# tinyLight_v1_1.net
KiCad netlist of a schematic drawn in EAGLE
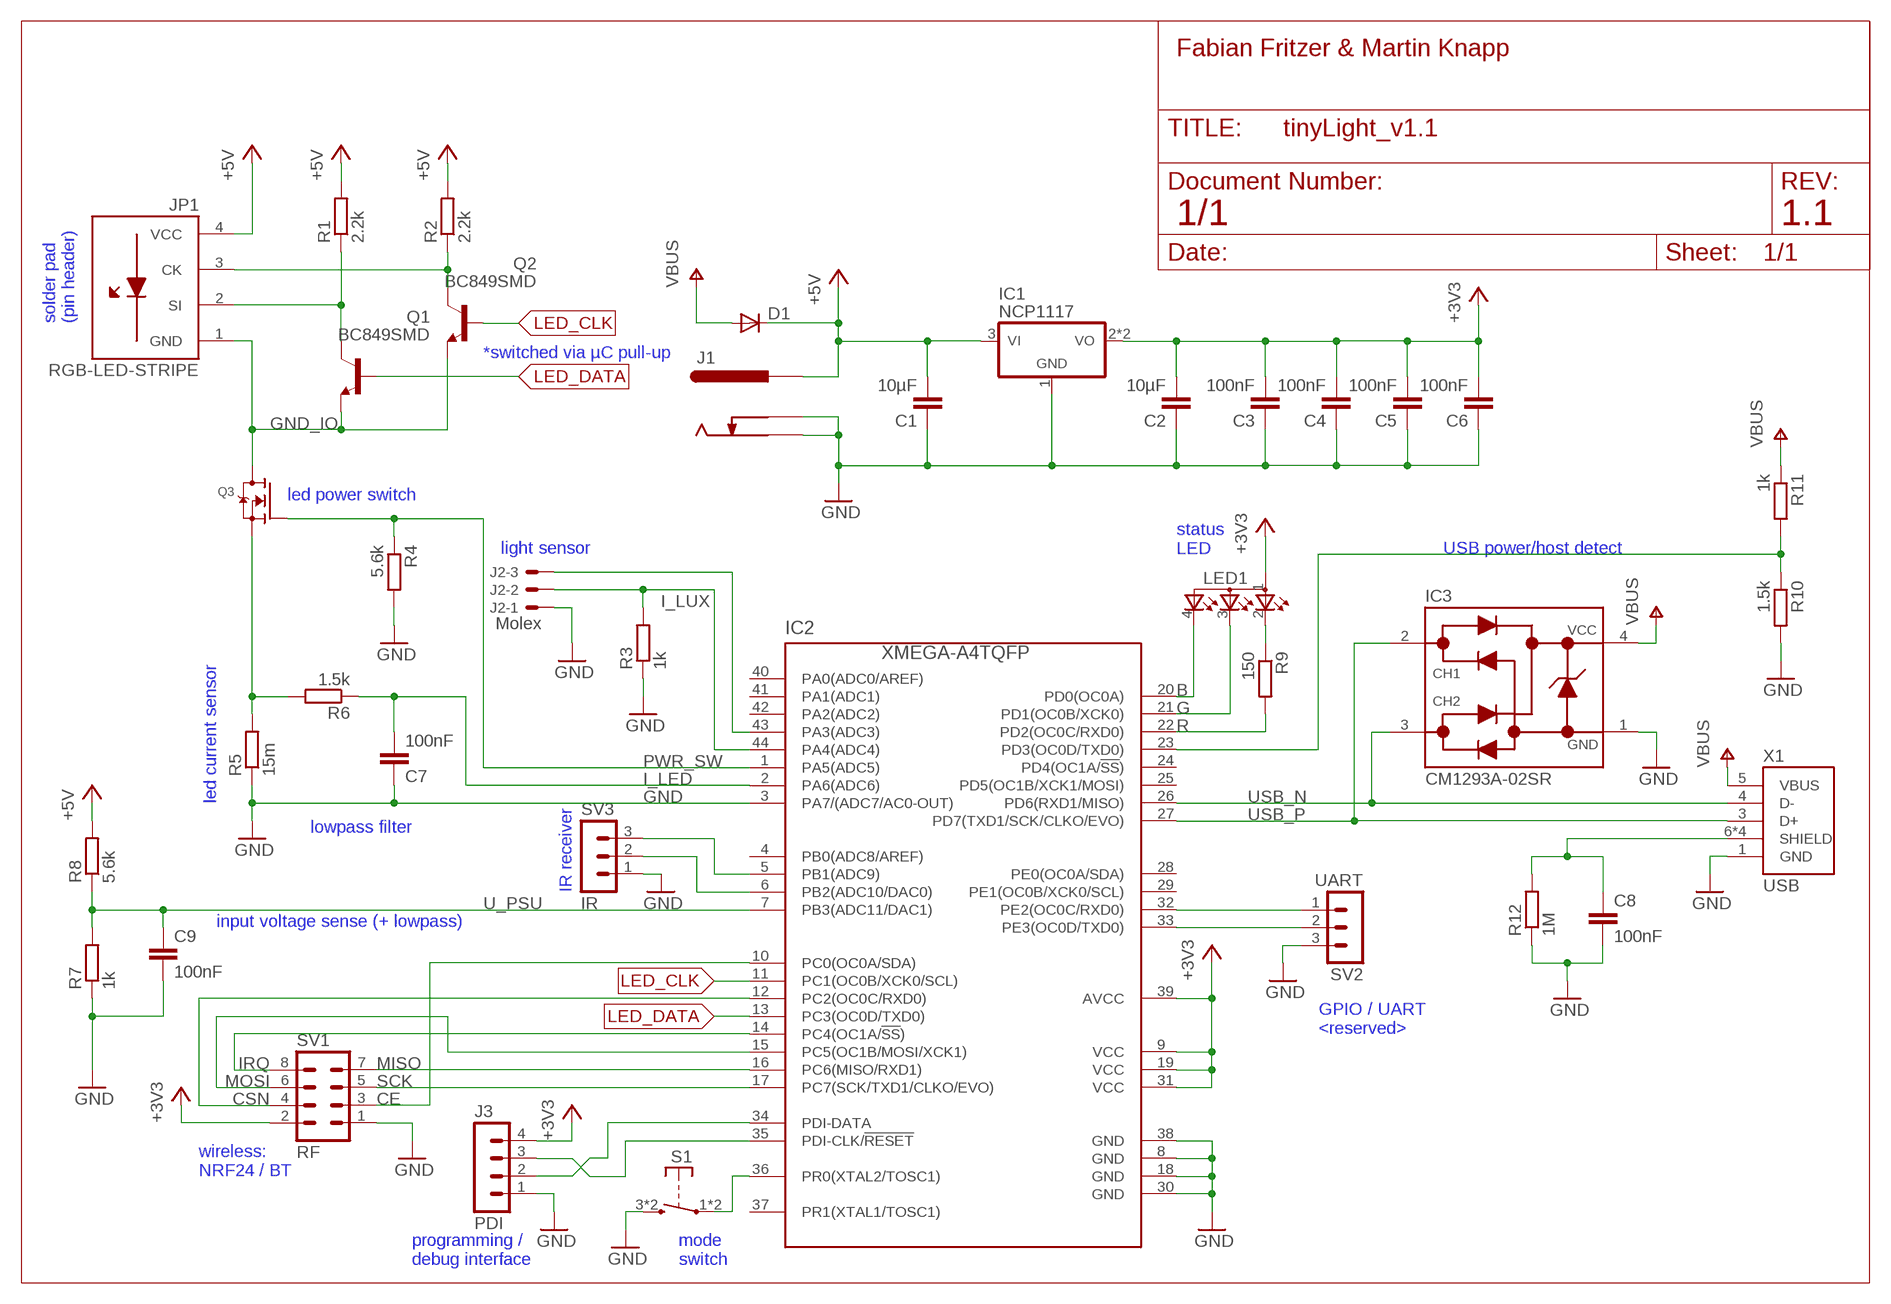
[diagram p0: schematic, sheet 1]

(export (version "E")
  (design (tool "Eeschema 10.0.6"))
  (components
    (comp (ref "C1")
      (value "10µF")
      (footprint "eagle-import:C2012")
      (libsource (lib "eagle-import") (part "C-EUC2012"))
    )
    (comp (ref "C2")
      (value "10µF")
      (footprint "eagle-import:C2012")
      (libsource (lib "eagle-import") (part "C-EUC2012"))
    )
    (comp (ref "C3")
      (value "100nF")
      (footprint "eagle-import:C2012")
      (libsource (lib "eagle-import") (part "C-EUC2012"))
    )
    (comp (ref "C4")
      (value "100nF")
      (footprint "eagle-import:C2012")
      (libsource (lib "eagle-import") (part "C-EUC2012"))
    )
    (comp (ref "C5")
      (value "100nF")
      (footprint "eagle-import:C2012")
      (libsource (lib "eagle-import") (part "C-EUC2012"))
    )
    (comp (ref "C6")
      (value "100nF")
      (footprint "eagle-import:C2012")
      (libsource (lib "eagle-import") (part "C-EUC2012"))
    )
    (comp (ref "C7")
      (value "100nF")
      (footprint "eagle-import:C2012")
      (libsource (lib "eagle-import") (part "C-EUC2012"))
    )
    (comp (ref "C8")
      (value "100nF")
      (footprint "eagle-import:C2012")
      (libsource (lib "eagle-import") (part "C-EUC2012"))
    )
    (comp (ref "C9")
      (value "100nF")
      (footprint "eagle-import:C2012")
      (libsource (lib "eagle-import") (part "C-EUC2012"))
    )
    (comp (ref "D1")
      (value "DIODE-DO-214AC")
      (footprint "eagle-import:DO-214AC")
      (libsource (lib "eagle-import") (part "DIODE-DO-214AC"))
    )
    (comp (ref "IC1")
      (value "NCP1117")
      (footprint "eagle-import:SOT223")
      (libsource (lib "eagle-import") (part "NCP1117"))
    )
    (comp (ref "IC2")
      (value "XMEGA-A4TQFP")
      (footprint "eagle-import:TQFP44")
      (libsource (lib "eagle-import") (part "XMEGA-A4TQFP"))
    )
    (comp (ref "IC3")
      (value "CM1293A-02SR")
      (footprint "eagle-import:SOT143")
      (libsource (lib "eagle-import") (part "CM1293A-02SR"))
    )
    (comp (ref "J1")
      (value "RASM722PX")
      (footprint "eagle-import:RASM722PX")
      (libsource (lib "eagle-import") (part "RASM722PX"))
    )
    (comp (ref "J2")
      (value "Molex")
      (footprint "eagle-import:6410-03")
      (libsource (lib "eagle-import") (part "22-?-0327-2031"))
    )
    (comp (ref "J3")
      (value "PDI")
      (footprint "eagle-import:MA04-1")
      (libsource (lib "eagle-import") (part "MA04-1"))
    )
    (comp (ref "JP1")
      (value "RGB-LED-STRIPE")
      (footprint "eagle-import:LED-STRIPE")
      (libsource (lib "eagle-import") (part "RGB-LED-STRIPE"))
    )
    (comp (ref "LED1")
      (value "RGB-LEDMINI")
      (footprint "eagle-import:P-LCC-4_M")
      (libsource (lib "eagle-import") (part "RGB-LEDMINI"))
    )
    (comp (ref "Q1")
      (value "BC849SMD")
      (footprint "eagle-import:SOT23-BEC")
      (libsource (lib "eagle-import") (part "BC849SMD"))
    )
    (comp (ref "Q2")
      (value "BC849SMD")
      (footprint "eagle-import:SOT23-BEC")
      (libsource (lib "eagle-import") (part "BC849SMD"))
    )
    (comp (ref "Q3")
      (value "MOSFET-N")
      (footprint "eagle-import:SOT457R_PHILIPS")
      (libsource (lib "eagle-import") (part "MOSFET-N"))
    )
    (comp (ref "R1")
      (value "2.2k")
      (footprint "eagle-import:M2012")
      (libsource (lib "eagle-import") (part "R-EU_M2012"))
    )
    (comp (ref "R2")
      (value "2.2k")
      (footprint "eagle-import:M2012")
      (libsource (lib "eagle-import") (part "R-EU_M2012"))
    )
    (comp (ref "R3")
      (value "1k")
      (footprint "eagle-import:M2012")
      (libsource (lib "eagle-import") (part "R-EU_M2012"))
    )
    (comp (ref "R4")
      (value "5.6k")
      (footprint "eagle-import:M2012")
      (libsource (lib "eagle-import") (part "R-EU_M2012"))
    )
    (comp (ref "R5")
      (value "15m")
      (footprint "eagle-import:M3216")
      (libsource (lib "eagle-import") (part "R-EU_M3216"))
    )
    (comp (ref "R6")
      (value "1.5k")
      (footprint "eagle-import:M2012")
      (libsource (lib "eagle-import") (part "R-EU_M2012"))
    )
    (comp (ref "R7")
      (value "1k")
      (footprint "eagle-import:M2012")
      (libsource (lib "eagle-import") (part "R-EU_M2012"))
    )
    (comp (ref "R8")
      (value "5.6k")
      (footprint "eagle-import:M2012")
      (libsource (lib "eagle-import") (part "R-EU_M2012"))
    )
    (comp (ref "R9")
      (value "150")
      (footprint "eagle-import:M2012")
      (libsource (lib "eagle-import") (part "R-EU_M2012"))
    )
    (comp (ref "R10")
      (value "1.5k")
      (footprint "eagle-import:M2012")
      (libsource (lib "eagle-import") (part "R-EU_M2012"))
    )
    (comp (ref "R11")
      (value "1k")
      (footprint "eagle-import:M2012")
      (libsource (lib "eagle-import") (part "R-EU_M2012"))
    )
    (comp (ref "R12")
      (value "1M")
      (footprint "eagle-import:M2012")
      (libsource (lib "eagle-import") (part "R-EU_M2012"))
    )
    (comp (ref "S1")
      (value "SPST_PB")
      (footprint "eagle-import:LSH_6X6")
      (libsource (lib "eagle-import") (part "SPST_PB"))
    )
    (comp (ref "SV1")
      (value "RF")
      (footprint "eagle-import:MA04-2")
      (libsource (lib "eagle-import") (part "MA04-2"))
    )
    (comp (ref "SV2")
      (value "UART")
      (footprint "eagle-import:MA03-1")
      (libsource (lib "eagle-import") (part "MA03-1"))
    )
    (comp (ref "SV3")
      (value "IR")
      (footprint "eagle-import:MA03-1")
      (libsource (lib "eagle-import") (part "MA03-1"))
    )
    (comp (ref "X1")
      (value "MICRO-USB")
      (footprint "eagle-import:MIKRO_B")
      (libsource (lib "eagle-import") (part "MICRO-USB"))
    )
  )
  (nets
    (net (code "1") (name "+3V3") (class "Default")
      (node (ref "C2") (pin "2") (pinfunction "2_2") (pintype "passive"))
      (node (ref "C3") (pin "2") (pinfunction "2_2") (pintype "passive"))
      (node (ref "C4") (pin "2") (pinfunction "2_2") (pintype "passive"))
      (node (ref "C5") (pin "2") (pinfunction "2_2") (pintype "passive"))
      (node (ref "C6") (pin "2") (pinfunction "2_2") (pintype "passive"))
      (node (ref "IC1") (pin "2") (pinfunction "VOUT_2") (pintype "output"))
      (node (ref "IC1") (pin "T") (pinfunction "VOUT_T") (pintype "output"))
      (node (ref "IC2") (pin "19") (pinfunction "VCC_19") (pintype "power_in"))
      (node (ref "IC2") (pin "31") (pinfunction "VCC_31") (pintype "power_in"))
      (node (ref "IC2") (pin "39") (pinfunction "AVCC_39") (pintype "power_in"))
      (node (ref "IC2") (pin "9") (pinfunction "VCC_9") (pintype "power_in"))
      (node (ref "J3") (pin "4") (pinfunction "4_4") (pintype "passive"))
      (node (ref "LED1") (pin "1") (pinfunction "ANODE_1") (pintype "passive"))
      (node (ref "SV1") (pin "2") (pinfunction "2_2") (pintype "passive"))
    )
    (net (code "2") (name "+5V") (class "Default")
      (node (ref "C1") (pin "2") (pinfunction "2_2") (pintype "passive"))
      (node (ref "D1") (pin "C") (pinfunction "C_C") (pintype "passive"))
      (node (ref "IC1") (pin "3") (pinfunction "VIN_3") (pintype "input"))
      (node (ref "J1") (pin "TIP") (pinfunction "TIP_TIP") (pintype "power_in"))
      (node (ref "JP1") (pin "4") (pinfunction "VCC_4") (pintype "power_in"))
      (node (ref "R1") (pin "2") (pinfunction "2_2") (pintype "passive"))
      (node (ref "R2") (pin "2") (pinfunction "2_2") (pintype "passive"))
      (node (ref "R8") (pin "2") (pinfunction "2_2") (pintype "passive"))
    )
    (net (code "3") (name "/B") (class "Default")
      (node (ref "IC2") (pin "20") (pinfunction "PD0(OC0A)_20") (pintype "bidirectional"))
      (node (ref "LED1") (pin "4") (pinfunction "CBLUE_4") (pintype "passive"))
    )
    (net (code "4") (name "/CE") (class "Default")
      (node (ref "IC2") (pin "10") (pinfunction "PC0(OC0A/SDA)_10") (pintype "bidirectional"))
      (node (ref "SV1") (pin "3") (pinfunction "3_3") (pintype "passive"))
    )
    (net (code "5") (name "/CSN") (class "Default")
      (node (ref "IC2") (pin "12") (pinfunction "PC2(OC0C/RXD0)_12") (pintype "bidirectional"))
      (node (ref "SV1") (pin "4") (pinfunction "4_4") (pintype "passive"))
    )
    (net (code "6") (name "/G") (class "Default")
      (node (ref "IC2") (pin "21") (pinfunction "PD1(OC0B/XCK0)_21") (pintype "bidirectional"))
      (node (ref "LED1") (pin "3") (pinfunction "CGREEN_3") (pintype "passive"))
    )
    (net (code "7") (name "/GND_IO") (class "Default")
      (node (ref "JP1") (pin "1") (pinfunction "GND_1") (pintype "power_in"))
      (node (ref "Q1") (pin "E") (pinfunction "E_E") (pintype "passive"))
      (node (ref "Q2") (pin "E") (pinfunction "E_E") (pintype "passive"))
      (node (ref "Q3") (pin "1") (pinfunction "D_1") (pintype "passive"))
      (node (ref "Q3") (pin "2") (pinfunction "D_2") (pintype "passive"))
      (node (ref "Q3") (pin "5") (pinfunction "D_5") (pintype "passive"))
      (node (ref "Q3") (pin "6") (pinfunction "D_6") (pintype "passive"))
    )
    (net (code "8") (name "/IRQ") (class "Default")
      (node (ref "IC2") (pin "14") (pinfunction "PC4(OC1A/~{SS})_14") (pintype "bidirectional"))
      (node (ref "SV1") (pin "8") (pinfunction "8_8") (pintype "passive"))
    )
    (net (code "9") (name "/I_LED") (class "Default")
      (node (ref "C7") (pin "2") (pinfunction "2_2") (pintype "passive"))
      (node (ref "IC2") (pin "2") (pinfunction "PA6(ADC6)_2") (pintype "bidirectional"))
      (node (ref "R6") (pin "1") (pinfunction "1_1") (pintype "passive"))
    )
    (net (code "10") (name "/I_LUX") (class "Default")
      (node (ref "IC2") (pin "44") (pinfunction "PA4(ADC4)_44") (pintype "bidirectional"))
      (node (ref "J2") (pin "2") (pinfunction "S_2") (pintype "passive"))
      (node (ref "R3") (pin "2") (pinfunction "2_2") (pintype "passive"))
    )
    (net (code "11") (name "/MISO") (class "Default")
      (node (ref "IC2") (pin "16") (pinfunction "PC6(MISO/RXD1)_16") (pintype "bidirectional"))
      (node (ref "SV1") (pin "7") (pinfunction "7_7") (pintype "passive"))
    )
    (net (code "12") (name "/MOSI") (class "Default")
      (node (ref "IC2") (pin "15") (pinfunction "PC5(OC1B/MOSI/XCK1)_15") (pintype "bidirectional"))
      (node (ref "SV1") (pin "6") (pinfunction "6_6") (pintype "passive"))
    )
    (net (code "13") (name "/PWR_SW") (class "Default")
      (node (ref "IC2") (pin "1") (pinfunction "PA5(ADC5)_1") (pintype "bidirectional"))
      (node (ref "Q3") (pin "3") (pinfunction "G_3") (pintype "passive"))
      (node (ref "R4") (pin "1") (pinfunction "1_1") (pintype "passive"))
    )
    (net (code "14") (name "/R") (class "Default")
      (node (ref "IC2") (pin "22") (pinfunction "PD2(OC0C/RXD0)_22") (pintype "bidirectional"))
      (node (ref "R9") (pin "2") (pinfunction "2_2") (pintype "passive"))
    )
    (net (code "15") (name "/SCK") (class "Default")
      (node (ref "IC2") (pin "17") (pinfunction "PC7(SCK/TXD1/CLKO/EVO)_17") (pintype "bidirectional"))
      (node (ref "SV1") (pin "5") (pinfunction "5_5") (pintype "passive"))
    )
    (net (code "16") (name "/USB_N") (class "Default")
      (node (ref "IC2") (pin "26") (pinfunction "PD6(RXD1/MISO)_26") (pintype "bidirectional"))
      (node (ref "IC3") (pin "3") (pinfunction "CH2_3") (pintype "bidirectional"))
      (node (ref "X1") (pin "4") (pinfunction "D-_4") (pintype "bidirectional"))
    )
    (net (code "17") (name "/USB_P") (class "Default")
      (node (ref "IC2") (pin "27") (pinfunction "PD7(TXD1/SCK/CLKO/EVO)_27") (pintype "bidirectional"))
      (node (ref "IC3") (pin "2") (pinfunction "CH1_2") (pintype "bidirectional"))
      (node (ref "X1") (pin "3") (pinfunction "D+_3") (pintype "bidirectional"))
    )
    (net (code "18") (name "/U_PSU") (class "Default")
      (node (ref "C9") (pin "1") (pinfunction "1_1") (pintype "passive"))
      (node (ref "IC2") (pin "7") (pinfunction "PB3(ADC11/DAC1)_7") (pintype "bidirectional"))
      (node (ref "R7") (pin "2") (pinfunction "2_2") (pintype "passive"))
      (node (ref "R8") (pin "1") (pinfunction "1_1") (pintype "passive"))
    )
    (net (code "19") (name "GND") (class "Default")
      (node (ref "C1") (pin "1") (pinfunction "1_1") (pintype "passive"))
      (node (ref "C2") (pin "1") (pinfunction "1_1") (pintype "passive"))
      (node (ref "C3") (pin "1") (pinfunction "1_1") (pintype "passive"))
      (node (ref "C4") (pin "1") (pinfunction "1_1") (pintype "passive"))
      (node (ref "C5") (pin "1") (pinfunction "1_1") (pintype "passive"))
      (node (ref "C6") (pin "1") (pinfunction "1_1") (pintype "passive"))
      (node (ref "C7") (pin "1") (pinfunction "1_1") (pintype "passive"))
      (node (ref "C8") (pin "2") (pinfunction "2_2") (pintype "passive"))
      (node (ref "C9") (pin "2") (pinfunction "2_2") (pintype "passive"))
      (node (ref "IC1") (pin "1") (pinfunction "GND_1") (pintype "power_in"))
      (node (ref "IC2") (pin "18") (pinfunction "GND_18") (pintype "power_in"))
      (node (ref "IC2") (pin "3") (pinfunction "PA7/(ADC7/AC0-OUT)_3") (pintype "bidirectional"))
      (node (ref "IC2") (pin "30") (pinfunction "GND_30") (pintype "power_in"))
      (node (ref "IC2") (pin "38") (pinfunction "GND_38") (pintype "power_in"))
      (node (ref "IC2") (pin "8") (pinfunction "GND_8") (pintype "power_in"))
      (node (ref "IC3") (pin "1") (pinfunction "GND_1") (pintype "power_in"))
      (node (ref "J1") (pin "SHUNT") (pinfunction "SHUNT_SHUNT") (pintype "power_in"))
      (node (ref "J1") (pin "SLEEVE") (pinfunction "SLEVE_SLEEVE") (pintype "bidirectional"))
      (node (ref "J2") (pin "1") (pinfunction "S_1") (pintype "passive"))
      (node (ref "J3") (pin "1") (pinfunction "1_1") (pintype "passive"))
      (node (ref "R10") (pin "2") (pinfunction "2_2") (pintype "passive"))
      (node (ref "R12") (pin "1") (pinfunction "1_1") (pintype "passive"))
      (node (ref "R3") (pin "1") (pinfunction "1_1") (pintype "passive"))
      (node (ref "R4") (pin "2") (pinfunction "2_2") (pintype "passive"))
      (node (ref "R5") (pin "1") (pinfunction "1_1") (pintype "passive"))
      (node (ref "R7") (pin "1") (pinfunction "1_1") (pintype "passive"))
      (node (ref "S1") (pin "3") (pinfunction "2_3") (pintype "passive"))
      (node (ref "S1") (pin "4") (pinfunction "2_4") (pintype "passive"))
      (node (ref "SV1") (pin "1") (pinfunction "1_1") (pintype "passive"))
      (node (ref "SV2") (pin "3") (pinfunction "3_3") (pintype "passive"))
      (node (ref "SV3") (pin "1") (pinfunction "1_1") (pintype "passive"))
      (node (ref "X1") (pin "1") (pinfunction "GND_1") (pintype "power_in"))
    )
    (net (code "20") (name "LED_CLK") (class "Default")
      (node (ref "IC2") (pin "11") (pinfunction "PC1(OC0B/XCK0/SCL)_11") (pintype "bidirectional"))
      (node (ref "Q2") (pin "B") (pinfunction "B_B") (pintype "passive"))
    )
    (net (code "21") (name "LED_DATA") (class "Default")
      (node (ref "IC2") (pin "13") (pinfunction "PC3(OC0D/TXD0)_13") (pintype "bidirectional"))
      (node (ref "Q1") (pin "B") (pinfunction "B_B") (pintype "passive"))
    )
    (net (code "22") (name "Net-(C8-Pad1)") (class "Default")
      (node (ref "C8") (pin "1") (pinfunction "1_1") (pintype "passive"))
      (node (ref "R12") (pin "2") (pinfunction "2_2") (pintype "passive"))
      (node (ref "X1") (pin "6") (pinfunction "SHIELD_6") (pintype "bidirectional"))
      (node (ref "X1") (pin "7") (pinfunction "SHIELD_7") (pintype "bidirectional"))
      (node (ref "X1") (pin "8") (pinfunction "SHIELD_8") (pintype "bidirectional"))
      (node (ref "X1") (pin "9") (pinfunction "SHIELD_9") (pintype "bidirectional"))
    )
    (net (code "23") (name "Net-(IC2-PA3(ADC3))") (class "Default")
      (node (ref "IC2") (pin "43") (pinfunction "PA3(ADC3)_43") (pintype "bidirectional"))
      (node (ref "J2") (pin "3") (pinfunction "S_3") (pintype "passive"))
    )
    (net (code "24") (name "Net-(IC2-PB1(ADC9))") (class "Default")
      (node (ref "IC2") (pin "5") (pinfunction "PB1(ADC9)_5") (pintype "bidirectional"))
      (node (ref "SV3") (pin "3") (pinfunction "3_3") (pintype "passive"))
    )
    (net (code "25") (name "Net-(IC2-PB2(ADC10{slash}DAC0))") (class "Default")
      (node (ref "IC2") (pin "6") (pinfunction "PB2(ADC10/DAC0)_6") (pintype "bidirectional"))
      (node (ref "SV3") (pin "2") (pinfunction "2_2") (pintype "passive"))
    )
    (net (code "26") (name "Net-(IC2-PD3(OC0D{slash}TXD0))") (class "Default")
      (node (ref "IC2") (pin "23") (pinfunction "PD3(OC0D/TXD0)_23") (pintype "bidirectional"))
      (node (ref "R10") (pin "1") (pinfunction "1_1") (pintype "passive"))
      (node (ref "R11") (pin "2") (pinfunction "2_2") (pintype "passive"))
    )
    (net (code "27") (name "Net-(IC2-PDI-CLK{slash}~{RESET})") (class "Default")
      (node (ref "IC2") (pin "35") (pinfunction "PDI-CLK/~{RESET}_35") (pintype "input"))
      (node (ref "J3") (pin "3") (pinfunction "3_3") (pintype "passive"))
    )
    (net (code "28") (name "Net-(IC2-PDI-DATA)") (class "Default")
      (node (ref "IC2") (pin "34") (pinfunction "PDI-DATA_34") (pintype "bidirectional"))
      (node (ref "J3") (pin "2") (pinfunction "2_2") (pintype "passive"))
    )
    (net (code "29") (name "Net-(IC2-PE2(OC0C{slash}RXD0))") (class "Default")
      (node (ref "IC2") (pin "32") (pinfunction "PE2(OC0C/RXD0)_32") (pintype "bidirectional"))
      (node (ref "SV2") (pin "1") (pinfunction "1_1") (pintype "passive"))
    )
    (net (code "30") (name "Net-(IC2-PE3(OC0D{slash}TXD0))") (class "Default")
      (node (ref "IC2") (pin "33") (pinfunction "PE3(OC0D/TXD0)_33") (pintype "bidirectional"))
      (node (ref "SV2") (pin "2") (pinfunction "2_2") (pintype "passive"))
    )
    (net (code "31") (name "Net-(IC2-PR0(XTAL2{slash}TOSC1))") (class "Default")
      (node (ref "IC2") (pin "36") (pinfunction "PR0(XTAL2/TOSC1)_36") (pintype "bidirectional"))
      (node (ref "S1") (pin "1") (pinfunction "1_1") (pintype "passive"))
      (node (ref "S1") (pin "2") (pinfunction "1_2") (pintype "passive"))
    )
    (net (code "32") (name "Net-(JP1-CK)") (class "Default")
      (node (ref "JP1") (pin "3") (pinfunction "CK_3") (pintype "input"))
      (node (ref "Q2") (pin "C") (pinfunction "C_C") (pintype "passive"))
      (node (ref "R2") (pin "1") (pinfunction "1_1") (pintype "passive"))
    )
    (net (code "33") (name "Net-(JP1-SI)") (class "Default")
      (node (ref "JP1") (pin "2") (pinfunction "SI_2") (pintype "input"))
      (node (ref "Q1") (pin "C") (pinfunction "C_C") (pintype "passive"))
      (node (ref "R1") (pin "1") (pinfunction "1_1") (pintype "passive"))
    )
    (net (code "34") (name "Net-(LED1-CRED)") (class "Default")
      (node (ref "LED1") (pin "2") (pinfunction "CRED_2") (pintype "passive"))
      (node (ref "R9") (pin "1") (pinfunction "1_1") (pintype "passive"))
    )
    (net (code "35") (name "Net-(Q3-S)") (class "Default")
      (node (ref "Q3") (pin "4") (pinfunction "S_4") (pintype "passive"))
      (node (ref "R5") (pin "2") (pinfunction "2_2") (pintype "passive"))
      (node (ref "R6") (pin "2") (pinfunction "2_2") (pintype "passive"))
    )
    (net (code "36") (name "VBUS") (class "Default")
      (node (ref "D1") (pin "A") (pinfunction "A_A") (pintype "passive"))
      (node (ref "IC3") (pin "4") (pinfunction "VCC_4") (pintype "power_in"))
      (node (ref "R11") (pin "1") (pinfunction "1_1") (pintype "passive"))
      (node (ref "X1") (pin "5") (pinfunction "VBUS_5") (pintype "bidirectional"))
    )
    (net (code "37") (name "unconnected-(IC2-PA0(ADC0{slash}AREF)-Pad40)") (class "Default")
      (node (ref "IC2") (pin "40") (pinfunction "PA0(ADC0/AREF)_40") (pintype "bidirectional"))
    )
    (net (code "38") (name "unconnected-(IC2-PA1(ADC1)-Pad41)") (class "Default")
      (node (ref "IC2") (pin "41") (pinfunction "PA1(ADC1)_41") (pintype "bidirectional"))
    )
    (net (code "39") (name "unconnected-(IC2-PA2(ADC2)-Pad42)") (class "Default")
      (node (ref "IC2") (pin "42") (pinfunction "PA2(ADC2)_42") (pintype "bidirectional"))
    )
    (net (code "40") (name "unconnected-(IC2-PB0(ADC8{slash}AREF)-Pad4)") (class "Default")
      (node (ref "IC2") (pin "4") (pinfunction "PB0(ADC8/AREF)_4") (pintype "bidirectional"))
    )
    (net (code "41") (name "unconnected-(IC2-PD4(OC1A{slash}~{SS})-Pad24)") (class "Default")
      (node (ref "IC2") (pin "24") (pinfunction "PD4(OC1A/~{SS})_24") (pintype "bidirectional"))
    )
    (net (code "42") (name "unconnected-(IC2-PD5(OC1B{slash}XCK1{slash}MOSI)-Pad25)") (class "Default")
      (node (ref "IC2") (pin "25") (pinfunction "PD5(OC1B/XCK1/MOSI)_25") (pintype "bidirectional"))
    )
    (net (code "43") (name "unconnected-(IC2-PE0(OC0A{slash}SDA)-Pad28)") (class "Default")
      (node (ref "IC2") (pin "28") (pinfunction "PE0(OC0A/SDA)_28") (pintype "bidirectional"))
    )
    (net (code "44") (name "unconnected-(IC2-PE1(OC0B{slash}XCK0{slash}SCL)-Pad29)") (class "Default")
      (node (ref "IC2") (pin "29") (pinfunction "PE1(OC0B/XCK0/SCL)_29") (pintype "bidirectional"))
    )
    (net (code "45") (name "unconnected-(IC2-PR1(XTAL1{slash}TOSC1)-Pad37)") (class "Default")
      (node (ref "IC2") (pin "37") (pinfunction "PR1(XTAL1/TOSC1)_37") (pintype "bidirectional"))
    )
  )
)
